# 1_Schematic.net
KiCad netlist of a schematic drawn in Altium Designer
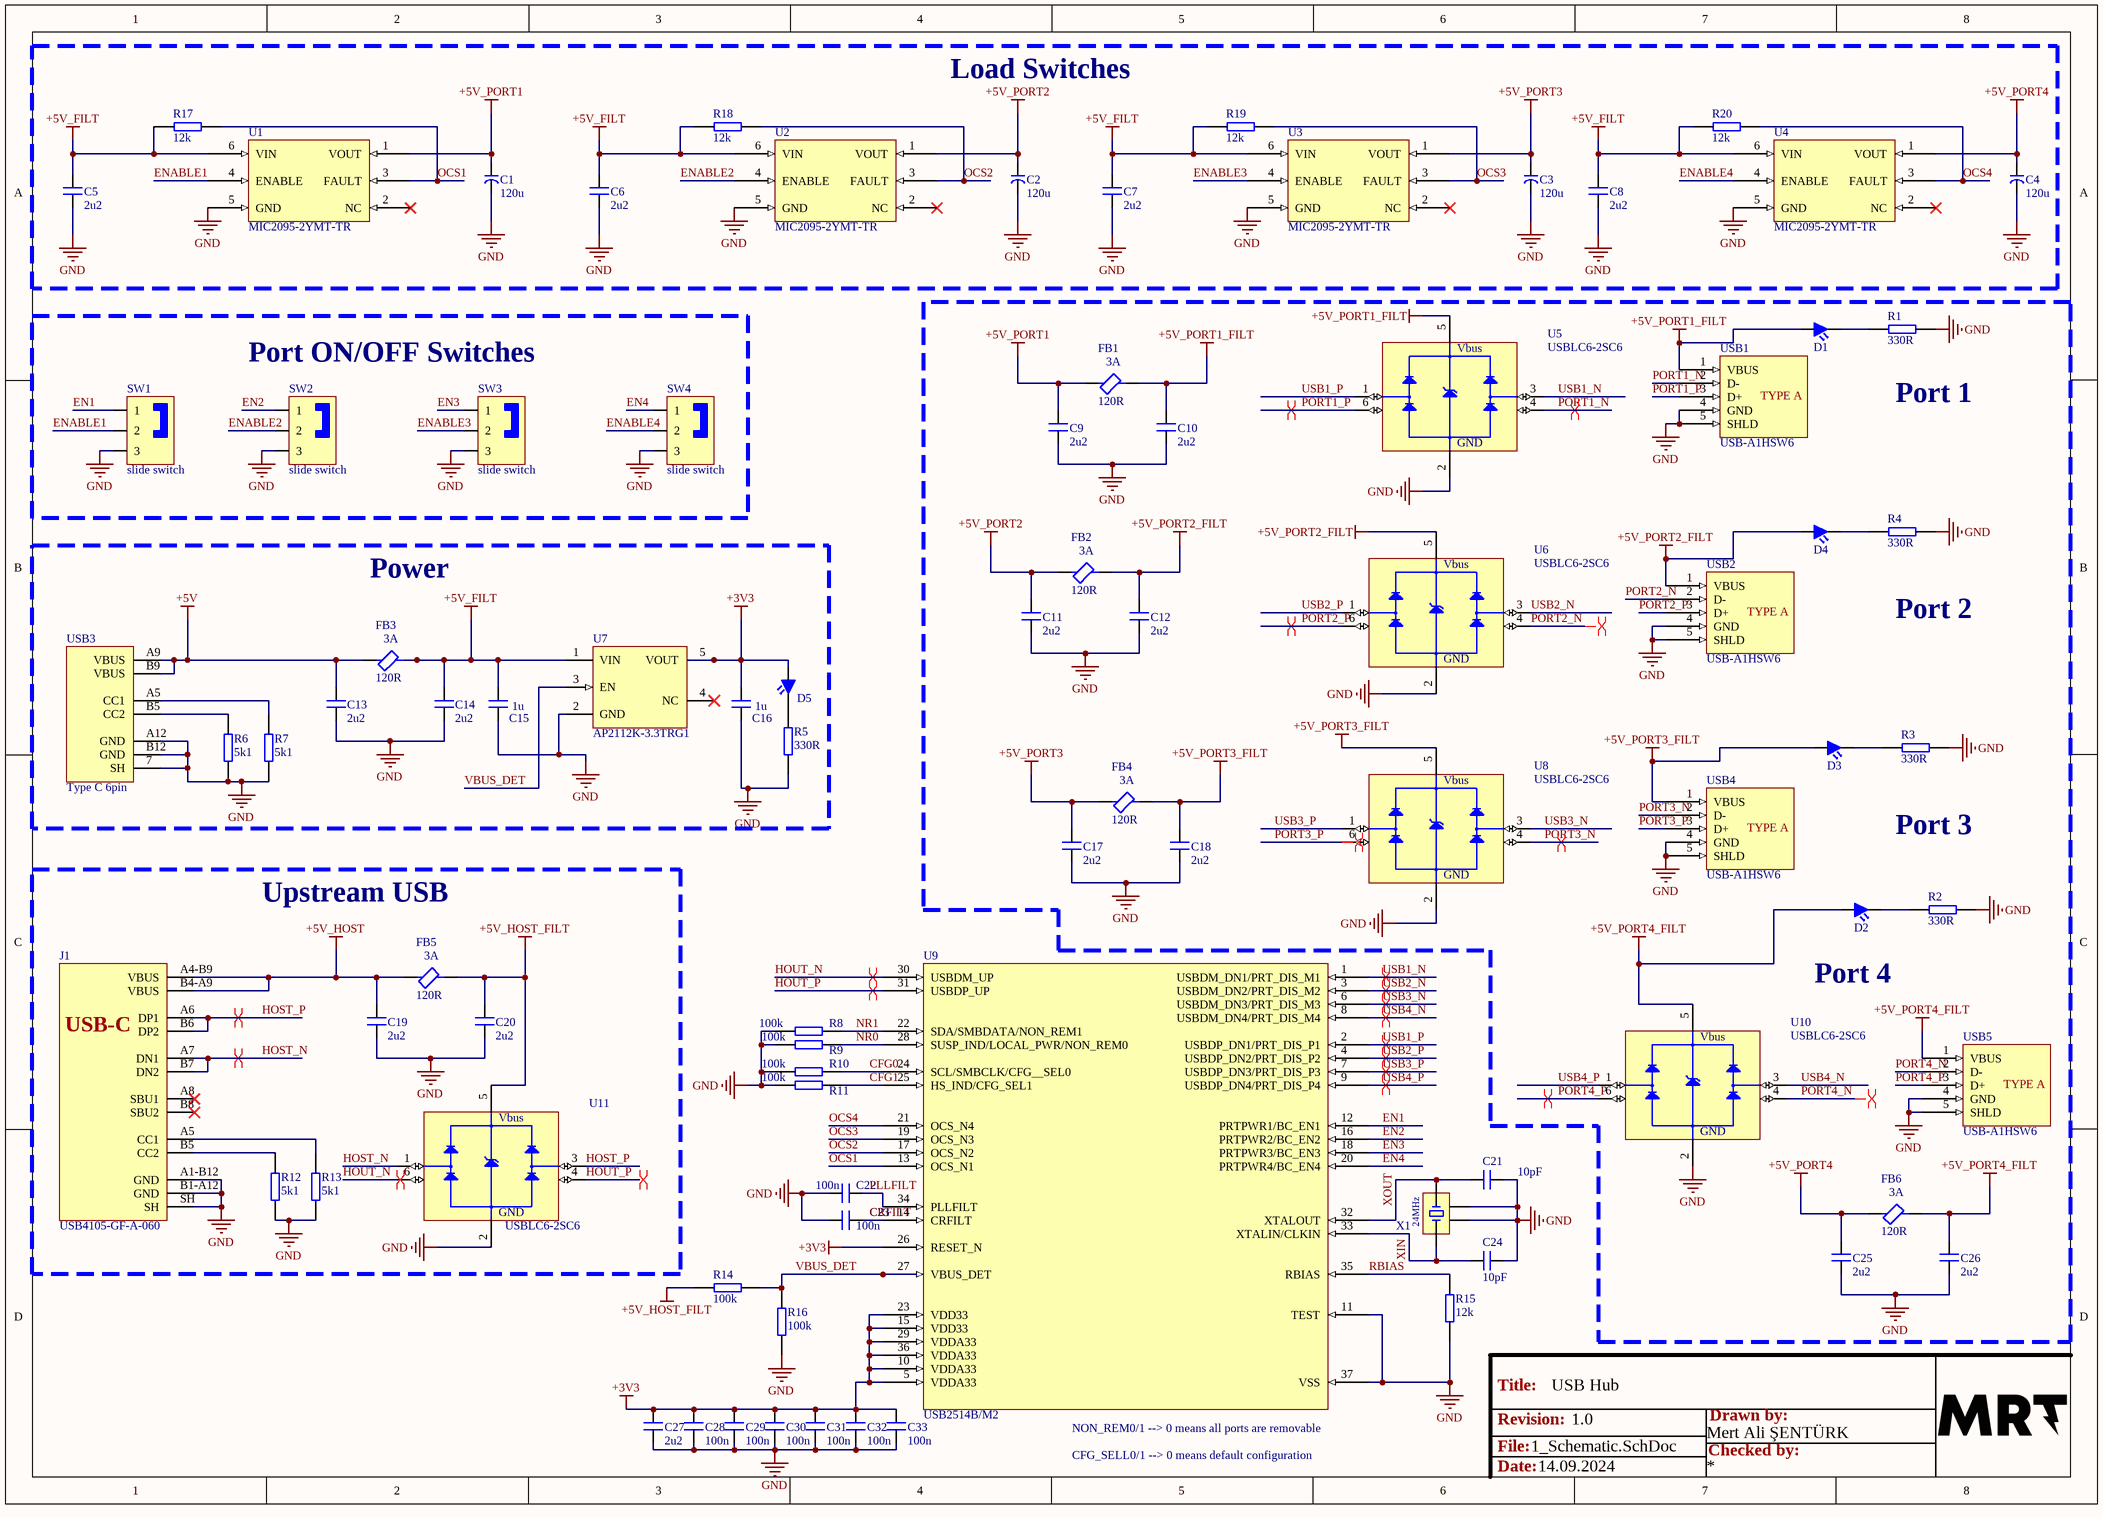
[diagram p0: 1_Schematic.SchDoc]

(export (version "E")
  (design (tool "Eeschema 10.0.6"))
  (components
    (comp (ref "C1")
      (value "120u")
      (footprint "6.30mm Radial, Can - SMD")
      (description "Aluminum Electrolytic Capacitor, 120 uF, 35 V, ± 20%, 2000 hours @ 105°C, Radial Can - SMD")
      (fields
        (field (name "MANUFACTURER") "Panasonic")
        (field (name "MANUFACTURER PART NUMBER") "EEE-FNV121XUP")
      )
      (libsource (lib "GenerALI") (part "CAP 120u Aluminum Electrolytic"))
    )
    (comp (ref "C2")
      (value "120u")
      (footprint "6.30mm Radial, Can - SMD")
      (description "Aluminum Electrolytic Capacitor, 120 uF, 35 V, ± 20%, 2000 hours @ 105°C, Radial Can - SMD")
      (fields
        (field (name "MANUFACTURER") "Panasonic")
        (field (name "MANUFACTURER PART NUMBER") "EEE-FNV121XUP")
      )
      (libsource (lib "GenerALI") (part "CAP 120u Aluminum Electrolytic"))
    )
    (comp (ref "C3")
      (value "120u")
      (footprint "6.30mm Radial, Can - SMD")
      (description "Aluminum Electrolytic Capacitor, 120 uF, 35 V, ± 20%, 2000 hours @ 105°C, Radial Can - SMD")
      (fields
        (field (name "MANUFACTURER") "Panasonic")
        (field (name "MANUFACTURER PART NUMBER") "EEE-FNV121XUP")
      )
      (libsource (lib "GenerALI") (part "CAP 120u Aluminum Electrolytic"))
    )
    (comp (ref "C4")
      (value "120u")
      (footprint "6.30mm Radial, Can - SMD")
      (description "Aluminum Electrolytic Capacitor, 120 uF, 35 V, ± 20%, 2000 hours @ 105°C, Radial Can - SMD")
      (fields
        (field (name "MANUFACTURER") "Panasonic")
        (field (name "MANUFACTURER PART NUMBER") "EEE-FNV121XUP")
      )
      (libsource (lib "GenerALI") (part "CAP 120u Aluminum Electrolytic"))
    )
    (comp (ref "C5") (value "2u2") (footprint "0603 CAP") (libsource (lib "GenerALI") (part "0603 2u2 CAP")))
    (comp (ref "C6") (value "2u2") (footprint "0603 CAP") (libsource (lib "GenerALI") (part "0603 2u2 CAP")))
    (comp (ref "C7") (value "2u2") (footprint "0603 CAP") (libsource (lib "GenerALI") (part "0603 2u2 CAP")))
    (comp (ref "C8") (value "2u2") (footprint "0603 CAP") (libsource (lib "GenerALI") (part "0603 2u2 CAP")))
    (comp (ref "C9") (value "2u2") (footprint "0603 CAP") (libsource (lib "GenerALI") (part "0603 2u2 CAP")))
    (comp (ref "C10") (value "2u2") (footprint "0603 CAP") (libsource (lib "GenerALI") (part "0603 2u2 CAP")))
    (comp (ref "C11") (value "2u2") (footprint "0603 CAP") (libsource (lib "GenerALI") (part "0603 2u2 CAP")))
    (comp (ref "C12") (value "2u2") (footprint "0603 CAP") (libsource (lib "GenerALI") (part "0603 2u2 CAP")))
    (comp (ref "C13") (value "2u2") (footprint "0603 CAP") (libsource (lib "GenerALI") (part "0603 2u2 CAP")))
    (comp (ref "C14") (value "2u2") (footprint "0603 CAP") (libsource (lib "GenerALI") (part "0603 2u2 CAP")))
    (comp (ref "C15")
      (value "1u")
      (footprint "0603 CAP")
      (fields
        (field (name "MANUFACTURER") "Murata")
        (field (name "MANUFACTURER PART NUMBER") "GCM188R71E105KA64D")
      )
      (libsource (lib "GenerALI") (part "0603 1u CAP"))
    )
    (comp (ref "C16")
      (value "1u")
      (footprint "0603 CAP")
      (fields
        (field (name "MANUFACTURER") "Murata")
        (field (name "MANUFACTURER PART NUMBER") "GCM188R71E105KA64D")
      )
      (libsource (lib "GenerALI") (part "0603 1u CAP"))
    )
    (comp (ref "C17") (value "2u2") (footprint "0603 CAP") (libsource (lib "GenerALI") (part "0603 2u2 CAP")))
    (comp (ref "C18") (value "2u2") (footprint "0603 CAP") (libsource (lib "GenerALI") (part "0603 2u2 CAP")))
    (comp (ref "C19") (value "2u2") (footprint "0603 CAP") (libsource (lib "GenerALI") (part "0603 2u2 CAP")))
    (comp (ref "C20") (value "2u2") (footprint "0603 CAP") (libsource (lib "GenerALI") (part "0603 2u2 CAP")))
    (comp (ref "C21")
      (value "10pF")
      (footprint "0402 CAP")
      (fields
        (field (name "MANUFACTURER") "Murata")
        (field (name "MANUFACTURER PART NUMBER") "GRM0225C1E100GA03L")
      )
      (libsource (lib "GenerALI") (part "0402 10p CAP"))
    )
    (comp (ref "C22")
      (value "100n")
      (footprint "0402 CAP")
      (fields
        (field (name "MANUFACTURER") "Murata")
        (field (name "MANUFACTURER PART NUMBER") "GRM155R71E104KE14J")
      )
      (libsource (lib "GenerALI") (part "0402 100n AP"))
    )
    (comp (ref "C23")
      (value "100n")
      (footprint "0402 CAP")
      (fields
        (field (name "MANUFACTURER") "Murata")
        (field (name "MANUFACTURER PART NUMBER") "GRM155R71E104KE14J")
      )
      (libsource (lib "GenerALI") (part "0402 100n AP"))
    )
    (comp (ref "C24")
      (value "10pF")
      (footprint "0402 CAP")
      (fields
        (field (name "MANUFACTURER") "Murata")
        (field (name "MANUFACTURER PART NUMBER") "GRM0225C1E100GA03L")
      )
      (libsource (lib "GenerALI") (part "0402 10p CAP"))
    )
    (comp (ref "C25") (value "2u2") (footprint "0603 CAP") (libsource (lib "GenerALI") (part "0603 2u2 CAP")))
    (comp (ref "C26") (value "2u2") (footprint "0603 CAP") (libsource (lib "GenerALI") (part "0603 2u2 CAP")))
    (comp (ref "C27") (value "2u2") (footprint "0603 CAP") (libsource (lib "GenerALI") (part "0603 2u2 CAP")))
    (comp (ref "C28")
      (value "100n")
      (footprint "0402 CAP")
      (fields
        (field (name "MANUFACTURER") "Murata")
        (field (name "MANUFACTURER PART NUMBER") "GRM155R71E104KE14J")
      )
      (libsource (lib "GenerALI") (part "0402 100n AP"))
    )
    (comp (ref "C29")
      (value "100n")
      (footprint "0402 CAP")
      (fields
        (field (name "MANUFACTURER") "Murata")
        (field (name "MANUFACTURER PART NUMBER") "GRM155R71E104KE14J")
      )
      (libsource (lib "GenerALI") (part "0402 100n AP"))
    )
    (comp (ref "C30")
      (value "100n")
      (footprint "0402 CAP")
      (fields
        (field (name "MANUFACTURER") "Murata")
        (field (name "MANUFACTURER PART NUMBER") "GRM155R71E104KE14J")
      )
      (libsource (lib "GenerALI") (part "0402 100n AP"))
    )
    (comp (ref "C31")
      (value "100n")
      (footprint "0402 CAP")
      (fields
        (field (name "MANUFACTURER") "Murata")
        (field (name "MANUFACTURER PART NUMBER") "GRM155R71E104KE14J")
      )
      (libsource (lib "GenerALI") (part "0402 100n AP"))
    )
    (comp (ref "C32")
      (value "100n")
      (footprint "0402 CAP")
      (fields
        (field (name "MANUFACTURER") "Murata")
        (field (name "MANUFACTURER PART NUMBER") "GRM155R71E104KE14J")
      )
      (libsource (lib "GenerALI") (part "0402 100n AP"))
    )
    (comp (ref "C33")
      (value "100n")
      (footprint "0402 CAP")
      (fields
        (field (name "MANUFACTURER") "Murata")
        (field (name "MANUFACTURER PART NUMBER") "GRM155R71E104KE14J")
      )
      (libsource (lib "GenerALI") (part "0402 100n AP"))
    )
    (comp (ref "D1")
      (value "LED GREEN 0805")
      (footprint "LED 0805")
      (libsource (lib "GenerALI") (part "LED GREEN 0805"))
    )
    (comp (ref "D2")
      (value "LED GREEN 0805")
      (footprint "LED 0805")
      (libsource (lib "GenerALI") (part "LED GREEN 0805"))
    )
    (comp (ref "D3")
      (value "LED GREEN 0805")
      (footprint "LED 0805")
      (libsource (lib "GenerALI") (part "LED GREEN 0805"))
    )
    (comp (ref "D4")
      (value "LED GREEN 0805")
      (footprint "LED 0805")
      (libsource (lib "GenerALI") (part "LED GREEN 0805"))
    )
    (comp (ref "D5")
      (value "LED RED 0805")
      (footprint "LED 0805")
      (libsource (lib "GenerALI") (part "LED RED 0805"))
    )
    (comp (ref "FB1")
      (value "120R")
      (footprint "0603 FB")
      (description "Ferrite Chip, 1 Function(s), 3A, 2 Pin(s)")
      (fields
        (field (name "MANUFACTURER") "Murata")
        (field (name "MANUFACTURER PART NUMBER") "BLM18KG121TN1D")
      )
      (libsource (lib "GenerALI") (part "BLM18KG121TN1D"))
    )
    (comp (ref "FB2")
      (value "120R")
      (footprint "0603 FB")
      (description "Ferrite Chip, 1 Function(s), 3A, 2 Pin(s)")
      (fields
        (field (name "MANUFACTURER") "Murata")
        (field (name "MANUFACTURER PART NUMBER") "BLM18KG121TN1D")
      )
      (libsource (lib "GenerALI") (part "BLM18KG121TN1D"))
    )
    (comp (ref "FB3")
      (value "120R")
      (footprint "0603 FB")
      (description "Ferrite Chip, 1 Function(s), 3A, 2 Pin(s)")
      (fields
        (field (name "MANUFACTURER") "Murata")
        (field (name "MANUFACTURER PART NUMBER") "BLM18KG121TN1D")
      )
      (libsource (lib "GenerALI") (part "BLM18KG121TN1D"))
    )
    (comp (ref "FB4")
      (value "120R")
      (footprint "0603 FB")
      (description "Ferrite Chip, 1 Function(s), 3A, 2 Pin(s)")
      (fields
        (field (name "MANUFACTURER") "Murata")
        (field (name "MANUFACTURER PART NUMBER") "BLM18KG121TN1D")
      )
      (libsource (lib "GenerALI") (part "BLM18KG121TN1D"))
    )
    (comp (ref "FB5")
      (value "120R")
      (footprint "0603 FB")
      (description "Ferrite Chip, 1 Function(s), 3A, 2 Pin(s)")
      (fields
        (field (name "MANUFACTURER") "Murata")
        (field (name "MANUFACTURER PART NUMBER") "BLM18KG121TN1D")
      )
      (libsource (lib "GenerALI") (part "BLM18KG121TN1D"))
    )
    (comp (ref "FB6")
      (value "120R")
      (footprint "0603 FB")
      (description "Ferrite Chip, 1 Function(s), 3A, 2 Pin(s)")
      (fields
        (field (name "MANUFACTURER") "Murata")
        (field (name "MANUFACTURER PART NUMBER") "BLM18KG121TN1D")
      )
      (libsource (lib "GenerALI") (part "BLM18KG121TN1D"))
    )
    (comp (ref "J1")
      (value "USB4105-GF-A-060")
      (footprint "USB TYPE C GCT 16P")
      (description "USB Connectors USB Type C, 2.0 SMT PCB Top Mnt .60mm")
      (fields (field (name "MANUFACTURER") "GCT"))
      (libsource (lib "GenerALI") (part "USB TYPE C 16 PIN GCT"))
    )
    (comp (ref "R1") (value "330R") (footprint "0402 RES") (libsource (lib "GenerALI") (part "0402 RES")))
    (comp (ref "R2") (value "330R") (footprint "0402 RES") (libsource (lib "GenerALI") (part "0402 RES")))
    (comp (ref "R3") (value "330R") (footprint "0402 RES") (libsource (lib "GenerALI") (part "0402 RES")))
    (comp (ref "R4") (value "330R") (footprint "0402 RES") (libsource (lib "GenerALI") (part "0402 RES")))
    (comp (ref "R5") (value "330R") (footprint "0402 RES") (libsource (lib "GenerALI") (part "0402 RES")))
    (comp (ref "R6") (value "5k1") (footprint "0402 RES") (libsource (lib "GenerALI") (part "0402 RES")))
    (comp (ref "R7") (value "5k1") (footprint "0402 RES") (libsource (lib "GenerALI") (part "0402 RES")))
    (comp (ref "R8") (value "100k") (footprint "0603 RES") (libsource (lib "GenerALI") (part "0603 0R RES")))
    (comp (ref "R9") (value "100k") (footprint "0603 RES") (libsource (lib "GenerALI") (part "0603 0R RES")))
    (comp (ref "R10") (value "100k") (footprint "0603 RES") (libsource (lib "GenerALI") (part "0603 0R RES")))
    (comp (ref "R11") (value "100k") (footprint "0603 RES") (libsource (lib "GenerALI") (part "0603 0R RES")))
    (comp (ref "R12") (value "5k1") (footprint "0402 RES") (libsource (lib "GenerALI") (part "0402 RES")))
    (comp (ref "R13") (value "5k1") (footprint "0402 RES") (libsource (lib "GenerALI") (part "0402 RES")))
    (comp (ref "R14") (value "100k") (footprint "0603 RES") (libsource (lib "GenerALI") (part "0603 0R RES")))
    (comp (ref "R15") (value "12k") (footprint "0603 RES") (libsource (lib "GenerALI") (part "0603 0R RES")))
    (comp (ref "R16") (value "100k") (footprint "0603 RES") (libsource (lib "GenerALI") (part "0603 0R RES")))
    (comp (ref "R17") (value "12k") (footprint "0603 RES") (libsource (lib "GenerALI") (part "0603 0R RES")))
    (comp (ref "R18") (value "12k") (footprint "0603 RES") (libsource (lib "GenerALI") (part "0603 0R RES")))
    (comp (ref "R19") (value "12k") (footprint "0603 RES") (libsource (lib "GenerALI") (part "0603 0R RES")))
    (comp (ref "R20") (value "12k") (footprint "0603 RES") (libsource (lib "GenerALI") (part "0603 0R RES")))
    (comp (ref "SW1")
      (value "slide switch")
      (footprint "EG1218")
      (fields (field (name "MANUFACTURER") "E-Switch") (field (name "MANUFACTURER PART NUMBER") "EG1218"))
      (libsource (lib "GenerALI") (part "slide switch"))
    )
    (comp (ref "SW2")
      (value "slide switch")
      (footprint "EG1218")
      (fields (field (name "MANUFACTURER") "E-Switch") (field (name "MANUFACTURER PART NUMBER") "EG1218"))
      (libsource (lib "GenerALI") (part "slide switch"))
    )
    (comp (ref "SW3")
      (value "slide switch")
      (footprint "EG1218")
      (fields (field (name "MANUFACTURER") "E-Switch") (field (name "MANUFACTURER PART NUMBER") "EG1218"))
      (libsource (lib "GenerALI") (part "slide switch"))
    )
    (comp (ref "SW4")
      (value "slide switch")
      (footprint "EG1218")
      (fields (field (name "MANUFACTURER") "E-Switch") (field (name "MANUFACTURER PART NUMBER") "EG1218"))
      (libsource (lib "GenerALI") (part "slide switch"))
    )
    (comp (ref "U1")
      (value "MIC2095-2YMT-TR")
      (footprint "6-UFDFN Exposed Pad")
      (description "Power Supply Support Circuit, 500mA Cuurent Fixed, 1 Channel, PDSO6")
      (fields (field (name "MANUFACTURER") "Microchip"))
      (libsource (lib "GenerALI") (part "MIC2095-2YMT-TR"))
    )
    (comp (ref "U2")
      (value "MIC2095-2YMT-TR")
      (footprint "6-UFDFN Exposed Pad")
      (description "Power Supply Support Circuit, 500mA Cuurent Fixed, 1 Channel, PDSO6")
      (fields (field (name "MANUFACTURER") "Microchip"))
      (libsource (lib "GenerALI") (part "MIC2095-2YMT-TR"))
    )
    (comp (ref "U3")
      (value "MIC2095-2YMT-TR")
      (footprint "6-UFDFN Exposed Pad")
      (description "Power Supply Support Circuit, 500mA Cuurent Fixed, 1 Channel, PDSO6")
      (fields (field (name "MANUFACTURER") "Microchip"))
      (libsource (lib "GenerALI") (part "MIC2095-2YMT-TR"))
    )
    (comp (ref "U4")
      (value "MIC2095-2YMT-TR")
      (footprint "6-UFDFN Exposed Pad")
      (description "Power Supply Support Circuit, 500mA Cuurent Fixed, 1 Channel, PDSO6")
      (fields (field (name "MANUFACTURER") "Microchip"))
      (libsource (lib "GenerALI") (part "MIC2095-2YMT-TR"))
    )
    (comp (ref "U5")
      (value "USBLC6-2SC6")
      (footprint "SOT23-6")
      (description "Trans Voltage Suppressor Diode, 5V V(RWM), Unidirectional, 1 Element, Silicon")
      (fields (field (name "MANUFACTURER") "STMicroelectronics"))
      (libsource (lib "GenerALI") (part "USBLC6-2SC6"))
    )
    (comp (ref "U6")
      (value "USBLC6-2SC6")
      (footprint "SOT23-6")
      (description "Trans Voltage Suppressor Diode, 5V V(RWM), Unidirectional, 1 Element, Silicon")
      (fields (field (name "MANUFACTURER") "STMicroelectronics"))
      (libsource (lib "GenerALI") (part "USBLC6-2SC6"))
    )
    (comp (ref "U7")
      (value "AP2112K-3.3TRG1")
      (footprint "SOT-23-5")
      (description "Fixed Positive LDO Regulator, 3.3V, 0.4V Dropout, CMOS, PDSO5 600mA")
      (fields (field (name "MANUFACTURER") "Diodes"))
      (libsource (lib "GenerALI") (part "AP2112K-3.3TRG1"))
    )
    (comp (ref "U8")
      (value "USBLC6-2SC6")
      (footprint "SOT23-6")
      (description "Trans Voltage Suppressor Diode, 5V V(RWM), Unidirectional, 1 Element, Silicon")
      (fields (field (name "MANUFACTURER") "STMicroelectronics"))
      (libsource (lib "GenerALI") (part "USBLC6-2SC6"))
    )
    (comp (ref "U9")
      (value "USB2514B/M2")
      (footprint "36-PIN SQFN")
      (description "USB Bus Controller, CMOS")
      (fields (field (name "MANUFACTURER") "Microchip"))
      (libsource (lib "GenerALI") (part "USB2514B/M2"))
    )
    (comp (ref "U10")
      (value "USBLC6-2SC6")
      (footprint "SOT23-6")
      (description "Trans Voltage Suppressor Diode, 5V V(RWM), Unidirectional, 1 Element, Silicon")
      (fields (field (name "MANUFACTURER") "STMicroelectronics"))
      (libsource (lib "GenerALI") (part "USBLC6-2SC6"))
    )
    (comp (ref "U11")
      (value "USBLC6-2SC6")
      (footprint "SOT23-6")
      (description "Trans Voltage Suppressor Diode, 5V V(RWM), Unidirectional, 1 Element, Silicon")
      (fields (field (name "MANUFACTURER") "STMicroelectronics"))
      (libsource (lib "GenerALI") (part "USBLC6-2SC6"))
    )
    (comp (ref "USB1")
      (value "USB-A1HSW6")
      (footprint "USB-A1HSW6")
      (description "USB Connector, 4 Contact(s), Female, Right Angle, Solder Terminal, Locking")
      (fields (field (name "MANUFACTURER") "On-Shore Technology"))
      (libsource (lib "GenerALI") (part "USB-A1HSW6"))
    )
    (comp (ref "USB2")
      (value "USB-A1HSW6")
      (footprint "USB-A1HSW6")
      (description "USB Connector, 4 Contact(s), Female, Right Angle, Solder Terminal, Locking")
      (fields (field (name "MANUFACTURER") "On-Shore Technology"))
      (libsource (lib "GenerALI") (part "USB-A1HSW6"))
    )
    (comp (ref "USB3")
      (value "Type C 6pin")
      (footprint "TYPE-C 6P(073)")
      (description "Manufacturer SHOU HAN\r\nMFR.Part # TYPE-C 6P(073)\r\nJLCPCB Part # C668623")
      (fields (field (name "MANUFACTURER") "SHOU HAN") (field (name "JLCPCB PART") "C668623"))
      (libsource (lib "GenerALI") (part "USB TYPE-C 6P(073) (Right Angle)"))
    )
    (comp (ref "USB4")
      (value "USB-A1HSW6")
      (footprint "USB-A1HSW6")
      (description "USB Connector, 4 Contact(s), Female, Right Angle, Solder Terminal, Locking")
      (fields (field (name "MANUFACTURER") "On-Shore Technology"))
      (libsource (lib "GenerALI") (part "USB-A1HSW6"))
    )
    (comp (ref "USB5")
      (value "USB-A1HSW6")
      (footprint "USB-A1HSW6")
      (description "USB Connector, 4 Contact(s), Female, Right Angle, Solder Terminal, Locking")
      (fields (field (name "MANUFACTURER") "On-Shore Technology"))
      (libsource (lib "GenerALI") (part "USB-A1HSW6"))
    )
    (comp (ref "X1")
      (value "TSX-3225 24.0000MF15X")
      (footprint "3225")
      (description "Crystals 24MHz 10ppm 9pF-40C +85C")
      (libsource (lib "GenerALI") (part "TSX-3225 24.0000MF15X-AC3"))
    )
  )
  (nets
    (net (code "1") (name "+3V3") (class "Default")
      (node (ref "C16") (pin "2") (pinfunction "2_2") (pintype "passive"))
      (node (ref "C27") (pin "2") (pinfunction "2_2") (pintype "passive"))
      (node (ref "C28") (pin "2") (pinfunction "2_2") (pintype "passive"))
      (node (ref "C29") (pin "2") (pinfunction "2_2") (pintype "passive"))
      (node (ref "C30") (pin "2") (pinfunction "2_2") (pintype "passive"))
      (node (ref "C31") (pin "2") (pinfunction "2_2") (pintype "passive"))
      (node (ref "C32") (pin "2") (pinfunction "2_2") (pintype "passive"))
      (node (ref "C33") (pin "2") (pinfunction "2_2") (pintype "passive"))
      (node (ref "D5") (pin "2") (pinfunction "2_2") (pintype "passive"))
      (node (ref "U7") (pin "5") (pinfunction "VOUT_5") (pintype "power_in"))
      (node (ref "U9") (pin "10") (pinfunction "VDDA33_10") (pintype "input"))
      (node (ref "U9") (pin "15") (pinfunction "VDD33_15") (pintype "input"))
      (node (ref "U9") (pin "23") (pinfunction "VDD33_23") (pintype "input"))
      (node (ref "U9") (pin "26") (pinfunction "RESET_N_26") (pintype "input"))
      (node (ref "U9") (pin "29") (pinfunction "VDDA33_29") (pintype "input"))
      (node (ref "U9") (pin "36") (pinfunction "VDDA33_36") (pintype "input"))
      (node (ref "U9") (pin "5") (pinfunction "VDDA33_5") (pintype "input"))
    )
    (net (code "2") (name "+5V") (class "Default")
      (node (ref "C13") (pin "2") (pinfunction "2_2") (pintype "passive"))
      (node (ref "FB3") (pin "1") (pinfunction "1_1") (pintype "passive"))
      (node (ref "USB3") (pin "A9") (pinfunction "VBUS_A9") (pintype "passive"))
      (node (ref "USB3") (pin "B9") (pinfunction "VBUS_B9") (pintype "passive"))
    )
    (net (code "3") (name "+5V_FILT") (class "Default")
      (node (ref "C14") (pin "2") (pinfunction "2_2") (pintype "passive"))
      (node (ref "C15") (pin "2") (pinfunction "2_2") (pintype "passive"))
      (node (ref "C5") (pin "1") (pinfunction "1_1") (pintype "passive"))
      (node (ref "C6") (pin "1") (pinfunction "1_1") (pintype "passive"))
      (node (ref "C7") (pin "1") (pinfunction "1_1") (pintype "passive"))
      (node (ref "C8") (pin "1") (pinfunction "1_1") (pintype "passive"))
      (node (ref "FB3") (pin "2") (pinfunction "2_2") (pintype "passive"))
      (node (ref "R17") (pin "2") (pinfunction "2_2") (pintype "passive"))
      (node (ref "R18") (pin "2") (pinfunction "2_2") (pintype "passive"))
      (node (ref "R19") (pin "2") (pinfunction "2_2") (pintype "passive"))
      (node (ref "R20") (pin "2") (pinfunction "2_2") (pintype "passive"))
      (node (ref "U1") (pin "6") (pinfunction "VIN_6") (pintype "input"))
      (node (ref "U2") (pin "6") (pinfunction "VIN_6") (pintype "input"))
      (node (ref "U3") (pin "6") (pinfunction "VIN_6") (pintype "input"))
      (node (ref "U4") (pin "6") (pinfunction "VIN_6") (pintype "input"))
      (node (ref "U7") (pin "1") (pinfunction "VIN_1") (pintype "power_in"))
    )
    (net (code "4") (name "+5V_HOST") (class "Default")
      (node (ref "C19") (pin "2") (pinfunction "2_2") (pintype "passive"))
      (node (ref "FB5") (pin "1") (pinfunction "1_1") (pintype "passive"))
      (node (ref "J1") (pin "A4-B9") (pinfunction "VBUS_A4-B9") (pintype "passive"))
      (node (ref "J1") (pin "B4-A9") (pinfunction "VBUS_B4-A9") (pintype "passive"))
    )
    (net (code "5") (name "+5V_HOST_FILT") (class "Default")
      (node (ref "C20") (pin "2") (pinfunction "2_2") (pintype "passive"))
      (node (ref "FB5") (pin "2") (pinfunction "2_2") (pintype "passive"))
      (node (ref "R14") (pin "2") (pinfunction "2_2") (pintype "passive"))
      (node (ref "U11") (pin "5") (pinfunction "VBUS_5") (pintype "power_in"))
    )
    (net (code "6") (name "+5V_PORT1") (class "Default")
      (node (ref "C1") (pin "2") (pinfunction "2_2") (pintype "passive"))
      (node (ref "C9") (pin "2") (pinfunction "2_2") (pintype "passive"))
      (node (ref "FB1") (pin "1") (pinfunction "1_1") (pintype "passive"))
      (node (ref "U1") (pin "1") (pinfunction "VOUT_1") (pintype "input"))
    )
    (net (code "7") (name "+5V_PORT1_FILT") (class "Default")
      (node (ref "C10") (pin "2") (pinfunction "2_2") (pintype "passive"))
      (node (ref "D1") (pin "2") (pinfunction "2_2") (pintype "passive"))
      (node (ref "FB1") (pin "2") (pinfunction "2_2") (pintype "passive"))
      (node (ref "U5") (pin "5") (pinfunction "VBUS_5") (pintype "power_in"))
      (node (ref "USB1") (pin "1") (pinfunction "VBUS_1") (pintype "input"))
    )
    (net (code "8") (name "+5V_PORT2") (class "Default")
      (node (ref "C11") (pin "2") (pinfunction "2_2") (pintype "passive"))
      (node (ref "C2") (pin "2") (pinfunction "2_2") (pintype "passive"))
      (node (ref "FB2") (pin "1") (pinfunction "1_1") (pintype "passive"))
      (node (ref "U2") (pin "1") (pinfunction "VOUT_1") (pintype "input"))
    )
    (net (code "9") (name "+5V_PORT2_FILT") (class "Default")
      (node (ref "C12") (pin "2") (pinfunction "2_2") (pintype "passive"))
      (node (ref "D4") (pin "2") (pinfunction "2_2") (pintype "passive"))
      (node (ref "FB2") (pin "2") (pinfunction "2_2") (pintype "passive"))
      (node (ref "U6") (pin "5") (pinfunction "VBUS_5") (pintype "power_in"))
      (node (ref "USB2") (pin "1") (pinfunction "VBUS_1") (pintype "input"))
    )
    (net (code "10") (name "+5V_PORT3") (class "Default")
      (node (ref "C17") (pin "2") (pinfunction "2_2") (pintype "passive"))
      (node (ref "C3") (pin "2") (pinfunction "2_2") (pintype "passive"))
      (node (ref "FB4") (pin "1") (pinfunction "1_1") (pintype "passive"))
      (node (ref "U3") (pin "1") (pinfunction "VOUT_1") (pintype "input"))
    )
    (net (code "11") (name "+5V_PORT3_FILT") (class "Default")
      (node (ref "C18") (pin "2") (pinfunction "2_2") (pintype "passive"))
      (node (ref "D3") (pin "2") (pinfunction "2_2") (pintype "passive"))
      (node (ref "FB4") (pin "2") (pinfunction "2_2") (pintype "passive"))
      (node (ref "U8") (pin "5") (pinfunction "VBUS_5") (pintype "power_in"))
      (node (ref "USB4") (pin "1") (pinfunction "VBUS_1") (pintype "input"))
    )
    (net (code "12") (name "+5V_PORT4") (class "Default")
      (node (ref "C25") (pin "2") (pinfunction "2_2") (pintype "passive"))
      (node (ref "C4") (pin "2") (pinfunction "2_2") (pintype "passive"))
      (node (ref "FB6") (pin "1") (pinfunction "1_1") (pintype "passive"))
      (node (ref "U4") (pin "1") (pinfunction "VOUT_1") (pintype "input"))
    )
    (net (code "13") (name "+5V_PORT4_FILT") (class "Default")
      (node (ref "C26") (pin "2") (pinfunction "2_2") (pintype "passive"))
      (node (ref "D2") (pin "2") (pinfunction "2_2") (pintype "passive"))
      (node (ref "FB6") (pin "2") (pinfunction "2_2") (pintype "passive"))
      (node (ref "U10") (pin "5") (pinfunction "VBUS_5") (pintype "power_in"))
      (node (ref "USB5") (pin "1") (pinfunction "VBUS_1") (pintype "input"))
    )
    (net (code "14") (name "/CFG0") (class "Default")
      (node (ref "R10") (pin "1") (pinfunction "1_1") (pintype "passive"))
      (node (ref "U9") (pin "24") (pinfunction "SCL/SMBCLK/CFG__SEL0_24") (pintype "input"))
    )
    (net (code "15") (name "/CFG1") (class "Default")
      (node (ref "R11") (pin "1") (pinfunction "1_1") (pintype "passive"))
      (node (ref "U9") (pin "25") (pinfunction "HS_IND/CFG_SEL1_25") (pintype "input"))
    )
    (net (code "16") (name "/CRFILT") (class "Default")
      (node (ref "C23") (pin "1") (pinfunction "1_1") (pintype "passive"))
      (node (ref "U9") (pin "14") (pinfunction "CRFILT_14") (pintype "input"))
    )
    (net (code "17") (name "/EN1") (class "Default")
      (node (ref "SW1") (pin "1") (pinfunction "1_1") (pintype "passive"))
      (node (ref "U9") (pin "12") (pinfunction "PRTPWR1/BC_EN1_12") (pintype "input"))
    )
    (net (code "18") (name "/EN2") (class "Default")
      (node (ref "SW2") (pin "1") (pinfunction "1_1") (pintype "passive"))
      (node (ref "U9") (pin "16") (pinfunction "PRTPWR2/BC_EN2_16") (pintype "input"))
    )
    (net (code "19") (name "/EN3") (class "Default")
      (node (ref "SW3") (pin "1") (pinfunction "1_1") (pintype "passive"))
      (node (ref "U9") (pin "18") (pinfunction "PRTPWR3/BC_EN3_18") (pintype "input"))
    )
    (net (code "20") (name "/EN4") (class "Default")
      (node (ref "SW4") (pin "1") (pinfunction "1_1") (pintype "passive"))
      (node (ref "U9") (pin "20") (pinfunction "PRTPWR4/BC_EN4_20") (pintype "input"))
    )
    (net (code "21") (name "/ENABLE1") (class "Default")
      (node (ref "SW1") (pin "2") (pinfunction "2_2") (pintype "passive"))
      (node (ref "U1") (pin "4") (pinfunction "ENABLE_4") (pintype "input"))
    )
    (net (code "22") (name "/ENABLE2") (class "Default")
      (node (ref "SW2") (pin "2") (pinfunction "2_2") (pintype "passive"))
      (node (ref "U2") (pin "4") (pinfunction "ENABLE_4") (pintype "input"))
    )
    (net (code "23") (name "/ENABLE3") (class "Default")
      (node (ref "SW3") (pin "2") (pinfunction "2_2") (pintype "passive"))
      (node (ref "U3") (pin "4") (pinfunction "ENABLE_4") (pintype "input"))
    )
    (net (code "24") (name "/ENABLE4") (class "Default")
      (node (ref "SW4") (pin "2") (pinfunction "2_2") (pintype "passive"))
      (node (ref "U4") (pin "4") (pinfunction "ENABLE_4") (pintype "input"))
    )
    (net (code "25") (name "/HOST_N") (class "Default")
      (node (ref "J1") (pin "A7") (pinfunction "DN1_A7") (pintype "passive"))
      (node (ref "J1") (pin "B7") (pinfunction "DN2_B7") (pintype "passive"))
      (node (ref "U11") (pin "1") (pinfunction "I/O1_1") (pintype "bidirectional"))
    )
    (net (code "26") (name "/HOST_P") (class "Default")
      (node (ref "J1") (pin "A6") (pinfunction "DP1_A6") (pintype "passive"))
      (node (ref "J1") (pin "B6") (pinfunction "DP2_B6") (pintype "passive"))
      (node (ref "U11") (pin "3") (pinfunction "I/O2_3") (pintype "bidirectional"))
    )
    (net (code "27") (name "/HOUT_N") (class "Default")
      (node (ref "U11") (pin "6") (pinfunction "I/O1_6") (pintype "bidirectional"))
      (node (ref "U9") (pin "30") (pinfunction "USBDM_UP_30") (pintype "input"))
    )
    (net (code "28") (name "/HOUT_P") (class "Default")
      (node (ref "U11") (pin "4") (pinfunction "I/O2_4") (pintype "bidirectional"))
      (node (ref "U9") (pin "31") (pinfunction "USBDP_UP_31") (pintype "input"))
    )
    (net (code "29") (name "/NR0") (class "Default")
      (node (ref "R9") (pin "1") (pinfunction "1_1") (pintype "passive"))
      (node (ref "U9") (pin "28") (pinfunction "SUSP_IND/LOCAL_PWR/NON_REM0_28") (pintype "input"))
    )
    (net (code "30") (name "/NR1") (class "Default")
      (node (ref "R8") (pin "1") (pinfunction "1_1") (pintype "passive"))
      (node (ref "U9") (pin "22") (pinfunction "SDA/SMBDATA/NON_REM1_22") (pintype "input"))
    )
    (net (code "31") (name "/OCS1") (class "Default")
      (node (ref "R17") (pin "1") (pinfunction "1_1") (pintype "passive"))
      (node (ref "U1") (pin "3") (pinfunction "FAULT_3") (pintype "input"))
      (node (ref "U9") (pin "13") (pinfunction "OCS_N1_13") (pintype "input"))
    )
    (net (code "32") (name "/OCS2") (class "Default")
      (node (ref "R18") (pin "1") (pinfunction "1_1") (pintype "passive"))
      (node (ref "U2") (pin "3") (pinfunction "FAULT_3") (pintype "input"))
      (node (ref "U9") (pin "17") (pinfunction "OCS_N2_17") (pintype "input"))
    )
    (net (code "33") (name "/OCS3") (class "Default")
      (node (ref "R19") (pin "1") (pinfunction "1_1") (pintype "passive"))
      (node (ref "U3") (pin "3") (pinfunction "FAULT_3") (pintype "input"))
      (node (ref "U9") (pin "19") (pinfunction "OCS_N3_19") (pintype "input"))
    )
    (net (code "34") (name "/OCS4") (class "Default")
      (node (ref "R20") (pin "1") (pinfunction "1_1") (pintype "passive"))
      (node (ref "U4") (pin "3") (pinfunction "FAULT_3") (pintype "input"))
      (node (ref "U9") (pin "21") (pinfunction "OCS_N4_21") (pintype "input"))
    )
    (net (code "35") (name "/PLLFILT") (class "Default")
      (node (ref "C22") (pin "1") (pinfunction "1_1") (pintype "passive"))
      (node (ref "U9") (pin "34") (pinfunction "PLLFILT_34") (pintype "input"))
    )
    (net (code "36") (name "/PORT1_N") (class "Default")
      (node (ref "U5") (pin "4") (pinfunction "I/O2_4") (pintype "bidirectional"))
      (node (ref "USB1") (pin "2") (pinfunction "D-_2") (pintype "input"))
    )
    (net (code "37") (name "/PORT1_P") (class "Default")
      (node (ref "U5") (pin "6") (pinfunction "I/O1_6") (pintype "bidirectional"))
      (node (ref "USB1") (pin "3") (pinfunction "D+_3") (pintype "input"))
    )
    (net (code "38") (name "/PORT2_N") (class "Default")
      (node (ref "U6") (pin "4") (pinfunction "I/O2_4") (pintype "bidirectional"))
      (node (ref "USB2") (pin "2") (pinfunction "D-_2") (pintype "input"))
    )
    (net (code "39") (name "/PORT2_P") (class "Default")
      (node (ref "U6") (pin "6") (pinfunction "I/O1_6") (pintype "bidirectional"))
      (node (ref "USB2") (pin "3") (pinfunction "D+_3") (pintype "input"))
    )
    (net (code "40") (name "/PORT3_N") (class "Default")
      (node (ref "U8") (pin "4") (pinfunction "I/O2_4") (pintype "bidirectional"))
      (node (ref "USB4") (pin "2") (pinfunction "D-_2") (pintype "input"))
    )
    (net (code "41") (name "/PORT3_P") (class "Default")
      (node (ref "U8") (pin "6") (pinfunction "I/O1_6") (pintype "bidirectional"))
      (node (ref "USB4") (pin "3") (pinfunction "D+_3") (pintype "input"))
    )
    (net (code "42") (name "/PORT4_N") (class "Default")
      (node (ref "U10") (pin "4") (pinfunction "I/O2_4") (pintype "bidirectional"))
      (node (ref "USB5") (pin "2") (pinfunction "D-_2") (pintype "input"))
    )
    (net (code "43") (name "/PORT4_P") (class "Default")
      (node (ref "U10") (pin "6") (pinfunction "I/O1_6") (pintype "bidirectional"))
      (node (ref "USB5") (pin "3") (pinfunction "D+_3") (pintype "input"))
    )
    (net (code "44") (name "/RBIAS") (class "Default")
      (node (ref "R15") (pin "2") (pinfunction "2_2") (pintype "passive"))
      (node (ref "U9") (pin "35") (pinfunction "RBIAS_35") (pintype "input"))
    )
    (net (code "45") (name "/USB1_N") (class "Default")
      (node (ref "U5") (pin "3") (pinfunction "I/O2_3") (pintype "bidirectional"))
      (node (ref "U9") (pin "1") (pinfunction "USBDM_DN1/PRT_DIS_M1_1") (pintype "input"))
    )
    (net (code "46") (name "/USB1_P") (class "Default")
      (node (ref "U5") (pin "1") (pinfunction "I/O1_1") (pintype "bidirectional"))
      (node (ref "U9") (pin "2") (pinfunction "USBDP_DN1/PRT_DIS_P1_2") (pintype "input"))
    )
    (net (code "47") (name "/USB2_N") (class "Default")
      (node (ref "U6") (pin "3") (pinfunction "I/O2_3") (pintype "bidirectional"))
      (node (ref "U9") (pin "3") (pinfunction "USBDM_DN2/PRT_DIS_M2_3") (pintype "input"))
    )
    (net (code "48") (name "/USB2_P") (class "Default")
      (node (ref "U6") (pin "1") (pinfunction "I/O1_1") (pintype "bidirectional"))
      (node (ref "U9") (pin "4") (pinfunction "USBDP_DN2/PRT_DIS_P2_4") (pintype "input"))
    )
    (net (code "49") (name "/USB3_N") (class "Default")
      (node (ref "U8") (pin "3") (pinfunction "I/O2_3") (pintype "bidirectional"))
      (node (ref "U9") (pin "6") (pinfunction "USBDM_DN3/PRT_DIS_M3_6") (pintype "input"))
    )
    (net (code "50") (name "/USB3_P") (class "Default")
      (node (ref "U8") (pin "1") (pinfunction "I/O1_1") (pintype "bidirectional"))
      (node (ref "U9") (pin "7") (pinfunction "USBDP_DN3/PRT_DIS_P3_7") (pintype "input"))
    )
    (net (code "51") (name "/USB4_N") (class "Default")
      (node (ref "U10") (pin "3") (pinfunction "I/O2_3") (pintype "bidirectional"))
      (node (ref "U9") (pin "8") (pinfunction "USBDM_DN4/PRT_DIS_M4_8") (pintype "input"))
    )
    (net (code "52") (name "/USB4_P") (class "Default")
      (node (ref "U10") (pin "1") (pinfunction "I/O1_1") (pintype "bidirectional"))
      (node (ref "U9") (pin "9") (pinfunction "USBDP_DN4/PRT_DIS_P4_9") (pintype "input"))
    )
    (net (code "53") (name "/VBUS_DET") (class "Default")
      (node (ref "R14") (pin "1") (pinfunction "1_1") (pintype "passive"))
      (node (ref "R16") (pin "2") (pinfunction "2_2") (pintype "passive"))
      (node (ref "U7") (pin "3") (pinfunction "EN_3") (pintype "input"))
      (node (ref "U9") (pin "27") (pinfunction "VBUS_DET_27") (pintype "input"))
    )
    (net (code "54") (name "/XIN") (class "Default")
      (node (ref "C24") (pin "1") (pinfunction "1_1") (pintype "passive"))
      (node (ref "U9") (pin "33") (pinfunction "XTALIN/CLKIN_33") (pintype "input"))
      (node (ref "X1") (pin "1") (pinfunction "1_1") (pintype "passive"))
    )
    (net (code "55") (name "/XOUT") (class "Default")
      (node (ref "C21") (pin "1") (pinfunction "1_1") (pintype "passive"))
      (node (ref "U9") (pin "32") (pinfunction "XTALOUT_32") (pintype "input"))
      (node (ref "X1") (pin "3") (pinfunction "3_3") (pintype "passive"))
    )
    (net (code "56") (name "GND") (class "Default")
      (node (ref "C1") (pin "1") (pinfunction "1_1") (pintype "passive"))
      (node (ref "C10") (pin "1") (pinfunction "1_1") (pintype "passive"))
      (node (ref "C11") (pin "1") (pinfunction "1_1") (pintype "passive"))
      (node (ref "C12") (pin "1") (pinfunction "1_1") (pintype "passive"))
      (node (ref "C13") (pin "1") (pinfunction "1_1") (pintype "passive"))
      (node (ref "C14") (pin "1") (pinfunction "1_1") (pintype "passive"))
      (node (ref "C15") (pin "1") (pinfunction "1_1") (pintype "passive"))
      (node (ref "C16") (pin "1") (pinfunction "1_1") (pintype "passive"))
      (node (ref "C17") (pin "1") (pinfunction "1_1") (pintype "passive"))
      (node (ref "C18") (pin "1") (pinfunction "1_1") (pintype "passive"))
      (node (ref "C19") (pin "1") (pinfunction "1_1") (pintype "passive"))
      (node (ref "C2") (pin "1") (pinfunction "1_1") (pintype "passive"))
      (node (ref "C20") (pin "1") (pinfunction "1_1") (pintype "passive"))
      (node (ref "C21") (pin "2") (pinfunction "2_2") (pintype "passive"))
      (node (ref "C22") (pin "2") (pinfunction "2_2") (pintype "passive"))
      (node (ref "C23") (pin "2") (pinfunction "2_2") (pintype "passive"))
      (node (ref "C24") (pin "2") (pinfunction "2_2") (pintype "passive"))
      (node (ref "C25") (pin "1") (pinfunction "1_1") (pintype "passive"))
      (node (ref "C26") (pin "1") (pinfunction "1_1") (pintype "passive"))
      (node (ref "C27") (pin "1") (pinfunction "1_1") (pintype "passive"))
      (node (ref "C28") (pin "1") (pinfunction "1_1") (pintype "passive"))
      (node (ref "C29") (pin "1") (pinfunction "1_1") (pintype "passive"))
      (node (ref "C3") (pin "1") (pinfunction "1_1") (pintype "passive"))
      (node (ref "C30") (pin "1") (pinfunction "1_1") (pintype "passive"))
      (node (ref "C31") (pin "1") (pinfunction "1_1") (pintype "passive"))
      (node (ref "C32") (pin "1") (pinfunction "1_1") (pintype "passive"))
      (node (ref "C33") (pin "1") (pinfunction "1_1") (pintype "passive"))
      (node (ref "C4") (pin "1") (pinfunction "1_1") (pintype "passive"))
      (node (ref "C5") (pin "2") (pinfunction "2_2") (pintype "passive"))
      (node (ref "C6") (pin "2") (pinfunction "2_2") (pintype "passive"))
      (node (ref "C7") (pin "2") (pinfunction "2_2") (pintype "passive"))
      (node (ref "C8") (pin "2") (pinfunction "2_2") (pintype "passive"))
      (node (ref "C9") (pin "1") (pinfunction "1_1") (pintype "passive"))
      (node (ref "J1") (pin "A1-B12") (pinfunction "GND_A1-B12") (pintype "passive"))
      (node (ref "J1") (pin "B1-A12") (pinfunction "GND_B1-A12") (pintype "passive"))
      (node (ref "J1") (pin "SH") (pinfunction "SH_SH") (pintype "passive"))
      (node (ref "R1") (pin "2") (pinfunction "2_2") (pintype "passive"))
      (node (ref "R10") (pin "2") (pinfunction "2_2") (pintype "passive"))
      (node (ref "R11") (pin "2") (pinfunction "2_2") (pintype "passive"))
      (node (ref "R12") (pin "1") (pinfunction "1_1") (pintype "passive"))
      (node (ref "R13") (pin "1") (pinfunction "1_1") (pintype "passive"))
      (node (ref "R15") (pin "1") (pinfunction "1_1") (pintype "passive"))
      (node (ref "R16") (pin "1") (pinfunction "1_1") (pintype "passive"))
      (node (ref "R2") (pin "2") (pinfunction "2_2") (pintype "passive"))
      (node (ref "R3") (pin "2") (pinfunction "2_2") (pintype "passive"))
      (node (ref "R4") (pin "2") (pinfunction "2_2") (pintype "passive"))
      (node (ref "R5") (pin "1") (pinfunction "1_1") (pintype "passive"))
      (node (ref "R6") (pin "1") (pinfunction "1_1") (pintype "passive"))
      (node (ref "R7") (pin "1") (pinfunction "1_1") (pintype "passive"))
      (node (ref "R8") (pin "2") (pinfunction "2_2") (pintype "passive"))
      (node (ref "R9") (pin "2") (pinfunction "2_2") (pintype "passive"))
      (node (ref "SW1") (pin "3") (pinfunction "3_3") (pintype "passive"))
      (node (ref "SW2") (pin "3") (pinfunction "3_3") (pintype "passive"))
      (node (ref "SW3") (pin "3") (pinfunction "3_3") (pintype "passive"))
      (node (ref "SW4") (pin "3") (pinfunction "3_3") (pintype "passive"))
      (node (ref "U1") (pin "5") (pinfunction "GND_5") (pintype "input"))
      (node (ref "U10") (pin "2") (pinfunction "GND_2") (pintype "power_in"))
      (node (ref "U11") (pin "2") (pinfunction "GND_2") (pintype "power_in"))
      (node (ref "U2") (pin "5") (pinfunction "GND_5") (pintype "input"))
      (node (ref "U3") (pin "5") (pinfunction "GND_5") (pintype "input"))
      (node (ref "U4") (pin "5") (pinfunction "GND_5") (pintype "input"))
      (node (ref "U5") (pin "2") (pinfunction "GND_2") (pintype "power_in"))
      (node (ref "U6") (pin "2") (pinfunction "GND_2") (pintype "power_in"))
      (node (ref "U7") (pin "2") (pinfunction "GND_2") (pintype "power_in"))
      (node (ref "U8") (pin "2") (pinfunction "GND_2") (pintype "power_in"))
      (node (ref "U9") (pin "11") (pinfunction "TEST_11") (pintype "input"))
      (node (ref "U9") (pin "37") (pinfunction "VSS_37") (pintype "input"))
      (node (ref "USB1") (pin "4") (pinfunction "GND_4") (pintype "input"))
      (node (ref "USB1") (pin "5") (pinfunction "SHLD_5") (pintype "input"))
      (node (ref "USB2") (pin "4") (pinfunction "GND_4") (pintype "input"))
      (node (ref "USB2") (pin "5") (pinfunction "SHLD_5") (pintype "input"))
      (node (ref "USB3") (pin "7") (pinfunction "SH_7") (pintype "passive"))
      (node (ref "USB3") (pin "A12") (pinfunction "GND_A12") (pintype "passive"))
      (node (ref "USB3") (pin "B12") (pinfunction "GND_B12") (pintype "passive"))
      (node (ref "USB4") (pin "4") (pinfunction "GND_4") (pintype "input"))
      (node (ref "USB4") (pin "5") (pinfunction "SHLD_5") (pintype "input"))
      (node (ref "USB5") (pin "4") (pinfunction "GND_4") (pintype "input"))
      (node (ref "USB5") (pin "5") (pinfunction "SHLD_5") (pintype "input"))
      (node (ref "X1") (pin "2") (pinfunction "2_2") (pintype "passive"))
      (node (ref "X1") (pin "4") (pinfunction "4_4") (pintype "passive"))
    )
    (net (code "57") (name "Net-(D1-Pad1)") (class "Default")
      (node (ref "D1") (pin "1") (pinfunction "1_1") (pintype "passive"))
      (node (ref "R1") (pin "1") (pinfunction "1_1") (pintype "passive"))
    )
    (net (code "58") (name "Net-(D2-Pad1)") (class "Default")
      (node (ref "D2") (pin "1") (pinfunction "1_1") (pintype "passive"))
      (node (ref "R2") (pin "1") (pinfunction "1_1") (pintype "passive"))
    )
    (net (code "59") (name "Net-(D3-Pad1)") (class "Default")
      (node (ref "D3") (pin "1") (pinfunction "1_1") (pintype "passive"))
      (node (ref "R3") (pin "1") (pinfunction "1_1") (pintype "passive"))
    )
    (net (code "60") (name "Net-(D4-Pad1)") (class "Default")
      (node (ref "D4") (pin "1") (pinfunction "1_1") (pintype "passive"))
      (node (ref "R4") (pin "1") (pinfunction "1_1") (pintype "passive"))
    )
    (net (code "61") (name "Net-(D5-Pad1)") (class "Default")
      (node (ref "D5") (pin "1") (pinfunction "1_1") (pintype "passive"))
      (node (ref "R5") (pin "2") (pinfunction "2_2") (pintype "passive"))
    )
    (net (code "62") (name "Net-(J1-CC1)") (class "Default")
      (node (ref "J1") (pin "A5") (pinfunction "CC1_A5") (pintype "passive"))
      (node (ref "R13") (pin "2") (pinfunction "2_2") (pintype "passive"))
    )
    (net (code "63") (name "Net-(J1-CC2)") (class "Default")
      (node (ref "J1") (pin "B5") (pinfunction "CC2_B5") (pintype "passive"))
      (node (ref "R12") (pin "2") (pinfunction "2_2") (pintype "passive"))
    )
    (net (code "64") (name "Net-(USB3-CC1)") (class "Default")
      (node (ref "R7") (pin "2") (pinfunction "2_2") (pintype "passive"))
      (node (ref "USB3") (pin "A5") (pinfunction "CC1_A5") (pintype "passive"))
    )
    (net (code "65") (name "Net-(USB3-CC2)") (class "Default")
      (node (ref "R6") (pin "2") (pinfunction "2_2") (pintype "passive"))
      (node (ref "USB3") (pin "B5") (pinfunction "CC2_B5") (pintype "passive"))
    )
    (net (code "66") (name "unconnected-(J1-SBU1-PadA8)") (class "Default")
      (node (ref "J1") (pin "A8") (pinfunction "SBU1_A8") (pintype "passive+no_connect"))
    )
    (net (code "67") (name "unconnected-(J1-SBU2-PadB8)") (class "Default")
      (node (ref "J1") (pin "B8") (pinfunction "SBU2_B8") (pintype "passive+no_connect"))
    )
    (net (code "68") (name "unconnected-(U1-NC-Pad2)") (class "Default")
      (node (ref "U1") (pin "2") (pinfunction "NC_2") (pintype "input+no_connect"))
    )
    (net (code "69") (name "unconnected-(U2-NC-Pad2)") (class "Default")
      (node (ref "U2") (pin "2") (pinfunction "NC_2") (pintype "input+no_connect"))
    )
    (net (code "70") (name "unconnected-(U3-NC-Pad2)") (class "Default")
      (node (ref "U3") (pin "2") (pinfunction "NC_2") (pintype "input+no_connect"))
    )
    (net (code "71") (name "unconnected-(U4-NC-Pad2)") (class "Default")
      (node (ref "U4") (pin "2") (pinfunction "NC_2") (pintype "input+no_connect"))
    )
    (net (code "72") (name "unconnected-(U7-NC-Pad4)") (class "Default")
      (node (ref "U7") (pin "4") (pinfunction "NC_4") (pintype "passive+no_connect"))
    )
  )
)
